# NBMC_SCHEMATIC_wout_thermistor_bridge.net
KiCad netlist of a schematic drawn in EAGLE
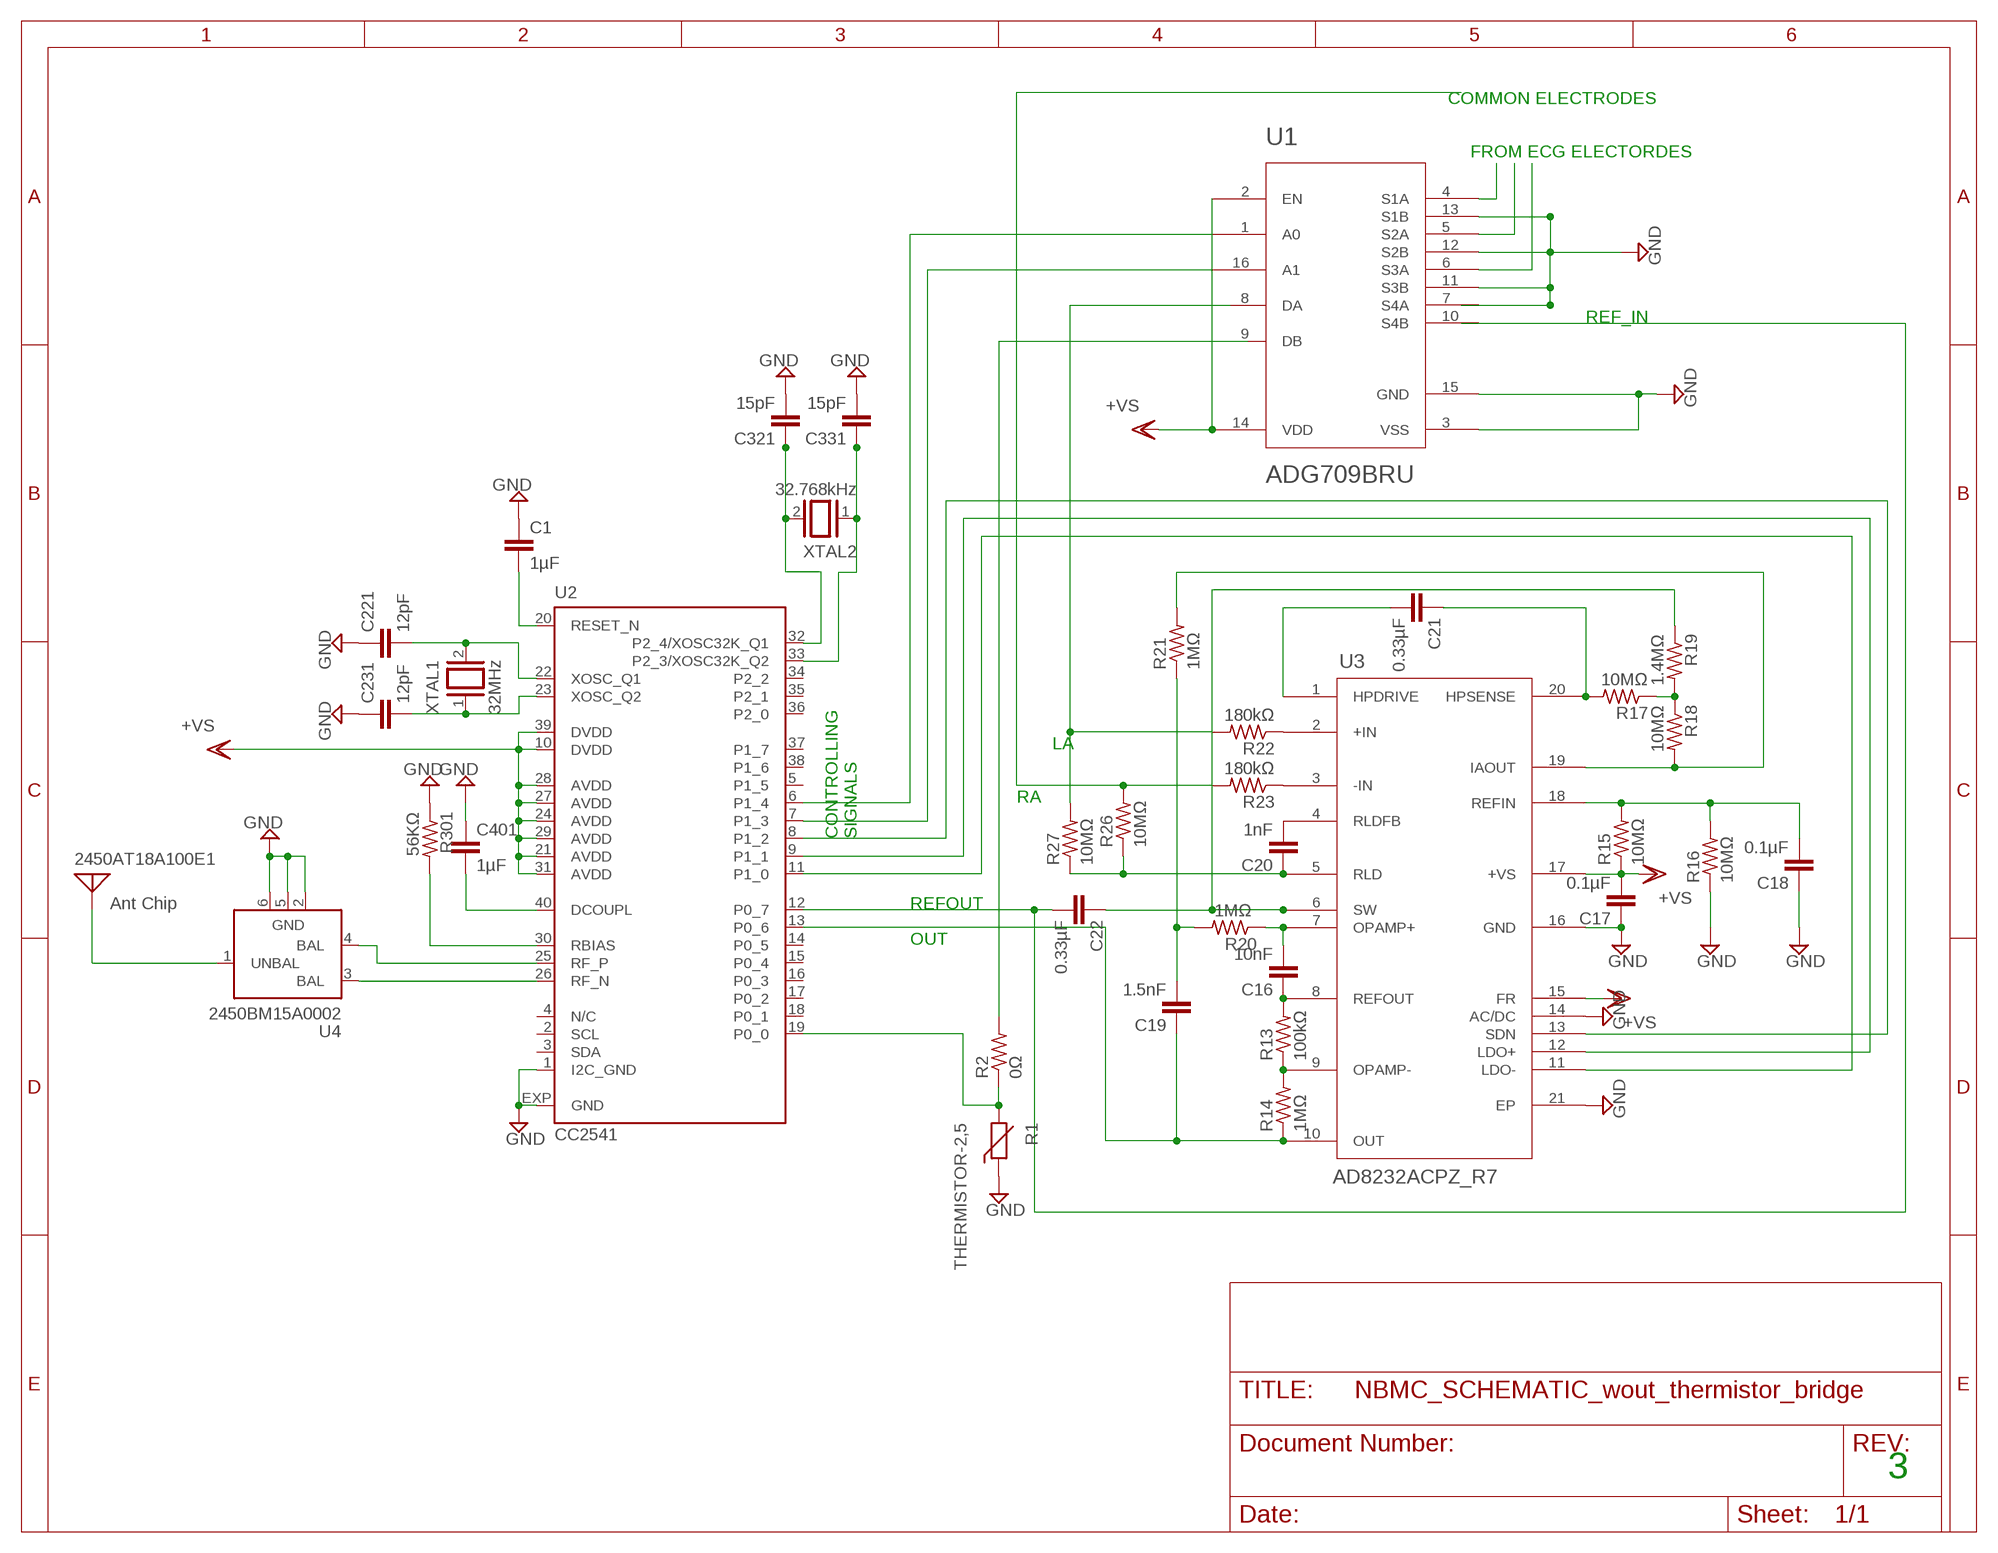
[diagram p0: schematic, sheet 1]

(export (version "E")
  (design (tool "Eeschema 10.0.6"))
  (components
    (comp (ref "2450AT18A100E1")
      (value "Ant Chip")
      (footprint "eagle-import:PAD-01")
      (libsource (lib "eagle-import") (part "ANTENNA"))
    )
    (comp (ref "C1")
      (value "1µF")
      (footprint "eagle-import:C0402")
      (libsource (lib "eagle-import") (part "C-EUC0402"))
    )
    (comp (ref "C16")
      (value "10nF")
      (footprint "eagle-import:C0402")
      (libsource (lib "eagle-import") (part "C-EUC0402"))
    )
    (comp (ref "C17")
      (value "0.1µF")
      (footprint "eagle-import:C0402")
      (libsource (lib "eagle-import") (part "C-EUC0402"))
    )
    (comp (ref "C18")
      (value "0.1µF")
      (footprint "eagle-import:C0402")
      (libsource (lib "eagle-import") (part "C-EUC0402"))
    )
    (comp (ref "C19")
      (value "1.5nF")
      (footprint "eagle-import:C0402")
      (libsource (lib "eagle-import") (part "C-EUC0402"))
    )
    (comp (ref "C20")
      (value "1nF")
      (footprint "eagle-import:C0402")
      (libsource (lib "eagle-import") (part "C-EUC0402"))
    )
    (comp (ref "C21")
      (value "0.33µF")
      (footprint "eagle-import:C0402")
      (libsource (lib "eagle-import") (part "C-EUC0402"))
    )
    (comp (ref "C22")
      (value "0.33µF")
      (footprint "eagle-import:C0402")
      (libsource (lib "eagle-import") (part "C-EUC0402"))
    )
    (comp (ref "C221")
      (value "12pF")
      (footprint "eagle-import:C0402")
      (libsource (lib "eagle-import") (part "C-EUC0402"))
    )
    (comp (ref "C231")
      (value "12pF")
      (footprint "eagle-import:C0402")
      (libsource (lib "eagle-import") (part "C-EUC0402"))
    )
    (comp (ref "C321")
      (value "15pF")
      (footprint "eagle-import:C0402")
      (libsource (lib "eagle-import") (part "C-EUC0402"))
    )
    (comp (ref "C331")
      (value "15pF")
      (footprint "eagle-import:C0402")
      (libsource (lib "eagle-import") (part "C-EUC0402"))
    )
    (comp (ref "C401")
      (value "1µF")
      (footprint "eagle-import:C0402")
      (libsource (lib "eagle-import") (part "C-EUC0402"))
    )
    (comp (ref "R1")
      (value "THERMISTOR-2,5")
      (footprint "eagle-import:RS-2,5")
      (libsource (lib "eagle-import") (part "THERMISTOR-2,5"))
    )
    (comp (ref "R2")
      (value "0Ω")
      (footprint "eagle-import:R0402")
      (libsource (lib "eagle-import") (part "R-US_R0402"))
    )
    (comp (ref "R13")
      (value "100kΩ")
      (footprint "eagle-import:R0402")
      (libsource (lib "eagle-import") (part "R-US_R0402"))
    )
    (comp (ref "R14")
      (value "1MΩ")
      (footprint "eagle-import:R0402")
      (libsource (lib "eagle-import") (part "R-US_R0402"))
    )
    (comp (ref "R15")
      (value "10MΩ")
      (footprint "eagle-import:R0402")
      (libsource (lib "eagle-import") (part "R-US_R0402"))
    )
    (comp (ref "R16")
      (value "10MΩ")
      (footprint "eagle-import:R0402")
      (libsource (lib "eagle-import") (part "R-US_R0402"))
    )
    (comp (ref "R17")
      (value "10MΩ")
      (footprint "eagle-import:R0402")
      (libsource (lib "eagle-import") (part "R-US_R0402"))
    )
    (comp (ref "R18")
      (value "10MΩ")
      (footprint "eagle-import:R0402")
      (libsource (lib "eagle-import") (part "R-US_R0402"))
    )
    (comp (ref "R19")
      (value "1.4MΩ")
      (footprint "eagle-import:R0402")
      (libsource (lib "eagle-import") (part "R-US_R0402"))
    )
    (comp (ref "R20")
      (value "1MΩ")
      (footprint "eagle-import:R0402")
      (libsource (lib "eagle-import") (part "R-US_R0402"))
    )
    (comp (ref "R21")
      (value "1MΩ")
      (footprint "eagle-import:R0402")
      (libsource (lib "eagle-import") (part "R-US_R0402"))
    )
    (comp (ref "R22")
      (value "180kΩ")
      (footprint "eagle-import:R0402")
      (libsource (lib "eagle-import") (part "R-US_R0402"))
    )
    (comp (ref "R23")
      (value "180kΩ")
      (footprint "eagle-import:R0402")
      (libsource (lib "eagle-import") (part "R-US_R0402"))
    )
    (comp (ref "R26")
      (value "10MΩ")
      (footprint "eagle-import:R0402")
      (libsource (lib "eagle-import") (part "R-US_R0402"))
    )
    (comp (ref "R27")
      (value "10MΩ")
      (footprint "eagle-import:R0402")
      (libsource (lib "eagle-import") (part "R-US_R0402"))
    )
    (comp (ref "R301")
      (value "56KΩ")
      (footprint "eagle-import:R0402")
      (libsource (lib "eagle-import") (part "R-US_R0402"))
    )
    (comp (ref "U1")
      (value "ADG709BRU")
      (footprint "eagle-import:RU_16")
      (libsource (lib "eagle-import") (part "ADG709BRU"))
    )
    (comp (ref "U2")
      (value "CC2541")
      (footprint "eagle-import:RHA_S-PVQFN-N40")
      (libsource (lib "eagle-import") (part "CC2541"))
    )
    (comp (ref "U3")
      (value "AD8232ACPZ_R7")
      (footprint "eagle-import:CP_20_10")
      (libsource (lib "eagle-import") (part "AD8232ACPZ_R7"))
    )
    (comp (ref "U4")
      (value "2450BM15A0002")
      (footprint "eagle-import:2450BM15A0002")
      (libsource (lib "eagle-import") (part "2450BM15A0002"))
    )
    (comp (ref "XTAL1")
      (value "32MHz")
      (footprint "eagle-import:Q")
      (libsource (lib "eagle-import") (part "XTAL"))
    )
    (comp (ref "XTAL2")
      (value "32.768kHz")
      (footprint "eagle-import:Q")
      (libsource (lib "eagle-import") (part "XTAL"))
    )
  )
  (nets
    (net (code "1") (name "+VS") (class "Default")
      (node (ref "C17") (pin "2") (pinfunction "2_2") (pintype "passive"))
      (node (ref "R15") (pin "1") (pinfunction "1_1") (pintype "passive"))
      (node (ref "U1") (pin "14") (pinfunction "VDD_14") (pintype "power_in"))
      (node (ref "U1") (pin "2") (pinfunction "EN_2") (pintype "passive"))
      (node (ref "U2") (pin "10") (pinfunction "DVDD_10") (pintype "power_in"))
      (node (ref "U2") (pin "21") (pinfunction "AVDD_21") (pintype "power_in"))
      (node (ref "U2") (pin "24") (pinfunction "AVDD_24") (pintype "power_in"))
      (node (ref "U2") (pin "27") (pinfunction "AVDD_27") (pintype "power_in"))
      (node (ref "U2") (pin "28") (pinfunction "AVDD_28") (pintype "power_in"))
      (node (ref "U2") (pin "29") (pinfunction "AVDD_29") (pintype "power_in"))
      (node (ref "U2") (pin "31") (pinfunction "AVDD_31") (pintype "power_in"))
      (node (ref "U2") (pin "39") (pinfunction "DVDD_39") (pintype "power_in"))
      (node (ref "U3") (pin "15") (pinfunction "FR_15") (pintype "passive"))
      (node (ref "U3") (pin "17") (pinfunction "+VS_17") (pintype "passive"))
    )
    (net (code "2") (name "/N{slash}C") (class "Default")
      (node (ref "U2") (pin "4") (pinfunction "N/C_4") (pintype "power_in"))
    )
    (net (code "3") (name "GND") (class "Default")
      (node (ref "C1") (pin "1") (pinfunction "1_1") (pintype "passive"))
      (node (ref "C17") (pin "1") (pinfunction "1_1") (pintype "passive"))
      (node (ref "C18") (pin "1") (pinfunction "1_1") (pintype "passive"))
      (node (ref "C221") (pin "1") (pinfunction "1_1") (pintype "passive"))
      (node (ref "C231") (pin "1") (pinfunction "1_1") (pintype "passive"))
      (node (ref "C321") (pin "2") (pinfunction "2_2") (pintype "passive"))
      (node (ref "C331") (pin "2") (pinfunction "2_2") (pintype "passive"))
      (node (ref "C401") (pin "1") (pinfunction "1_1") (pintype "passive"))
      (node (ref "R1") (pin "1") (pinfunction "1_1") (pintype "passive"))
      (node (ref "R16") (pin "1") (pinfunction "1_1") (pintype "passive"))
      (node (ref "R301") (pin "1") (pinfunction "1_1") (pintype "passive"))
      (node (ref "U1") (pin "11") (pinfunction "S3B_11") (pintype "passive"))
      (node (ref "U1") (pin "12") (pinfunction "S2B_12") (pintype "passive"))
      (node (ref "U1") (pin "13") (pinfunction "S1B_13") (pintype "passive"))
      (node (ref "U1") (pin "15") (pinfunction "GND_15") (pintype "passive"))
      (node (ref "U1") (pin "3") (pinfunction "VSS_3") (pintype "power_in"))
      (node (ref "U2") (pin "1") (pinfunction "I2C_GND_1") (pintype "power_in"))
      (node (ref "U2") (pin "EXP") (pinfunction "GND_EXP") (pintype "passive"))
      (node (ref "U3") (pin "14") (pinfunction "AC/DC_14") (pintype "passive"))
      (node (ref "U3") (pin "16") (pinfunction "GND_16") (pintype "passive"))
      (node (ref "U3") (pin "21") (pinfunction "EP_21") (pintype "passive"))
      (node (ref "U4") (pin "2") (pinfunction "GND_2") (pintype "passive"))
      (node (ref "U4") (pin "5") (pinfunction "GND_5") (pintype "passive"))
      (node (ref "U4") (pin "6") (pinfunction "GND_6") (pintype "passive"))
    )
    (net (code "4") (name "Net-(C19-Pad2)") (class "Default")
      (node (ref "C19") (pin "2") (pinfunction "2_2") (pintype "passive"))
      (node (ref "R20") (pin "2") (pinfunction "2_2") (pintype "passive"))
      (node (ref "R21") (pin "1") (pinfunction "1_1") (pintype "passive"))
    )
    (net (code "5") (name "Net-(R17-Pad1)") (class "Default")
      (node (ref "R17") (pin "1") (pinfunction "1_1") (pintype "passive"))
      (node (ref "R18") (pin "1") (pinfunction "1_1") (pintype "passive"))
      (node (ref "R19") (pin "2") (pinfunction "2_2") (pintype "passive"))
    )
    (net (code "6") (name "Net-(R22-Pad2)") (class "Default")
      (node (ref "R22") (pin "2") (pinfunction "2_2") (pintype "passive"))
      (node (ref "R27") (pin "2") (pinfunction "2_2") (pintype "passive"))
    )
    (net (code "7") (name "Net-(R23-Pad2)") (class "Default")
      (node (ref "R23") (pin "2") (pinfunction "2_2") (pintype "passive"))
      (node (ref "R26") (pin "2") (pinfunction "2_2") (pintype "passive"))
    )
    (net (code "8") (name "Net-(U1-A0)") (class "Default")
      (node (ref "U1") (pin "1") (pinfunction "A0_1") (pintype "passive"))
      (node (ref "U2") (pin "6") (pinfunction "P1_4_6") (pintype "bidirectional"))
    )
    (net (code "9") (name "Net-(U1-A1)") (class "Default")
      (node (ref "U1") (pin "16") (pinfunction "A1_16") (pintype "passive"))
      (node (ref "U2") (pin "7") (pinfunction "P1_3_7") (pintype "bidirectional"))
    )
    (net (code "10") (name "Net-(U1-S4B)") (class "Default")
      (node (ref "C22") (pin "2") (pinfunction "2_2") (pintype "passive"))
      (node (ref "U1") (pin "10") (pinfunction "S4B_10") (pintype "passive"))
      (node (ref "U2") (pin "12") (pinfunction "P0_7_12") (pintype "bidirectional"))
    )
    (net (code "11") (name "Net-(U2-DCOUPL)") (class "Default")
      (node (ref "C401") (pin "2") (pinfunction "2_2") (pintype "passive"))
      (node (ref "U2") (pin "40") (pinfunction "DCOUPL_40") (pintype "power_in"))
    )
    (net (code "12") (name "Net-(U2-P0_0)") (class "Default")
      (node (ref "R1") (pin "2") (pinfunction "2_2") (pintype "passive"))
      (node (ref "R2") (pin "1") (pinfunction "1_1") (pintype "passive"))
      (node (ref "U2") (pin "19") (pinfunction "P0_0_19") (pintype "bidirectional"))
    )
    (net (code "13") (name "Net-(U2-P0_6)") (class "Default")
      (node (ref "C19") (pin "1") (pinfunction "1_1") (pintype "passive"))
      (node (ref "R14") (pin "1") (pinfunction "1_1") (pintype "passive"))
      (node (ref "U2") (pin "13") (pinfunction "P0_6_13") (pintype "bidirectional"))
      (node (ref "U3") (pin "10") (pinfunction "OUT_10") (pintype "passive"))
    )
    (net (code "14") (name "Net-(U2-P1_0)") (class "Default")
      (node (ref "U2") (pin "11") (pinfunction "P1_0_11") (pintype "bidirectional"))
      (node (ref "U3") (pin "11") (pinfunction "LDO-_11") (pintype "passive"))
    )
    (net (code "15") (name "Net-(U2-P1_1)") (class "Default")
      (node (ref "U2") (pin "9") (pinfunction "P1_1_9") (pintype "bidirectional"))
      (node (ref "U3") (pin "12") (pinfunction "LDO+_12") (pintype "passive"))
    )
    (net (code "16") (name "Net-(U2-P1_2)") (class "Default")
      (node (ref "U2") (pin "8") (pinfunction "P1_2_8") (pintype "bidirectional"))
      (node (ref "U3") (pin "13") (pinfunction "SDN_13") (pintype "passive"))
    )
    (net (code "17") (name "Net-(U2-P2_3{slash}XOSC32K_Q2)") (class "Default")
      (node (ref "C331") (pin "1") (pinfunction "1_1") (pintype "passive"))
      (node (ref "U2") (pin "33") (pinfunction "P2_3/XOSC32K_Q2_33") (pintype "bidirectional"))
      (node (ref "XTAL2") (pin "1") (pinfunction "1_1") (pintype "passive"))
    )
    (net (code "18") (name "Net-(U2-P2_4{slash}XOSC32K_Q1)") (class "Default")
      (node (ref "C321") (pin "1") (pinfunction "1_1") (pintype "passive"))
      (node (ref "U2") (pin "32") (pinfunction "P2_4/XOSC32K_Q1_32") (pintype "bidirectional"))
      (node (ref "XTAL2") (pin "2") (pinfunction "2_2") (pintype "passive"))
    )
    (net (code "19") (name "Net-(U2-RBIAS)") (class "Default")
      (node (ref "R301") (pin "2") (pinfunction "2_2") (pintype "passive"))
      (node (ref "U2") (pin "30") (pinfunction "RBIAS_30") (pintype "bidirectional"))
    )
    (net (code "20") (name "Net-(U2-RESET_N)") (class "Default")
      (node (ref "C1") (pin "2") (pinfunction "2_2") (pintype "passive"))
      (node (ref "U2") (pin "20") (pinfunction "RESET_N_20") (pintype "input"))
    )
    (net (code "21") (name "Net-(U2-RF_N)") (class "Default")
      (node (ref "U2") (pin "26") (pinfunction "RF_N_26") (pintype "bidirectional"))
      (node (ref "U4") (pin "3") (pinfunction "BAL_3") (pintype "passive"))
    )
    (net (code "22") (name "Net-(U2-RF_P)") (class "Default")
      (node (ref "U2") (pin "25") (pinfunction "RF_P_25") (pintype "bidirectional"))
      (node (ref "U4") (pin "4") (pinfunction "BAL_4") (pintype "passive"))
    )
    (net (code "23") (name "Net-(U2-XOSC_Q1)") (class "Default")
      (node (ref "C221") (pin "2") (pinfunction "2_2") (pintype "passive"))
      (node (ref "U2") (pin "22") (pinfunction "XOSC_Q1_22") (pintype "bidirectional"))
      (node (ref "XTAL1") (pin "2") (pinfunction "2_2") (pintype "passive"))
    )
    (net (code "24") (name "Net-(U2-XOSC_Q2)") (class "Default")
      (node (ref "C231") (pin "2") (pinfunction "2_2") (pintype "passive"))
      (node (ref "U2") (pin "23") (pinfunction "XOSC_Q2_23") (pintype "bidirectional"))
      (node (ref "XTAL1") (pin "1") (pinfunction "1_1") (pintype "passive"))
    )
    (net (code "25") (name "Net-(U3-+IN)") (class "Default")
      (node (ref "R22") (pin "1") (pinfunction "1_1") (pintype "passive"))
      (node (ref "U3") (pin "2") (pinfunction "+IN_2") (pintype "passive"))
    )
    (net (code "26") (name "Net-(U3--IN)") (class "Default")
      (node (ref "R23") (pin "1") (pinfunction "1_1") (pintype "passive"))
      (node (ref "U3") (pin "3") (pinfunction "-IN_3") (pintype "passive"))
    )
    (net (code "27") (name "Net-(U3-HPDRIVE)") (class "Default")
      (node (ref "C21") (pin "2") (pinfunction "2_2") (pintype "passive"))
      (node (ref "U3") (pin "1") (pinfunction "HPDRIVE_1") (pintype "passive"))
    )
    (net (code "28") (name "Net-(U3-HPSENSE)") (class "Default")
      (node (ref "C21") (pin "1") (pinfunction "1_1") (pintype "passive"))
      (node (ref "R17") (pin "2") (pinfunction "2_2") (pintype "passive"))
      (node (ref "U3") (pin "20") (pinfunction "HPSENSE_20") (pintype "passive"))
    )
    (net (code "29") (name "Net-(U3-IAOUT)") (class "Default")
      (node (ref "R18") (pin "2") (pinfunction "2_2") (pintype "passive"))
      (node (ref "R21") (pin "2") (pinfunction "2_2") (pintype "passive"))
      (node (ref "U3") (pin "19") (pinfunction "IAOUT_19") (pintype "passive"))
    )
    (net (code "30") (name "Net-(U3-OPAMP+)") (class "Default")
      (node (ref "C16") (pin "2") (pinfunction "2_2") (pintype "passive"))
      (node (ref "R20") (pin "1") (pinfunction "1_1") (pintype "passive"))
      (node (ref "U3") (pin "7") (pinfunction "OPAMP+_7") (pintype "passive"))
    )
    (net (code "31") (name "Net-(U3-OPAMP-)") (class "Default")
      (node (ref "R13") (pin "1") (pinfunction "1_1") (pintype "passive"))
      (node (ref "R14") (pin "2") (pinfunction "2_2") (pintype "passive"))
      (node (ref "U3") (pin "9") (pinfunction "OPAMP-_9") (pintype "passive"))
    )
    (net (code "32") (name "Net-(U3-REFIN)") (class "Default")
      (node (ref "C18") (pin "2") (pinfunction "2_2") (pintype "passive"))
      (node (ref "R15") (pin "2") (pinfunction "2_2") (pintype "passive"))
      (node (ref "R16") (pin "2") (pinfunction "2_2") (pintype "passive"))
      (node (ref "U3") (pin "18") (pinfunction "REFIN_18") (pintype "passive"))
    )
    (net (code "33") (name "Net-(U3-REFOUT)") (class "Default")
      (node (ref "C16") (pin "1") (pinfunction "1_1") (pintype "passive"))
      (node (ref "R13") (pin "2") (pinfunction "2_2") (pintype "passive"))
      (node (ref "U3") (pin "8") (pinfunction "REFOUT_8") (pintype "passive"))
    )
    (net (code "34") (name "Net-(U3-RLD)") (class "Default")
      (node (ref "C20") (pin "1") (pinfunction "1_1") (pintype "passive"))
      (node (ref "R26") (pin "1") (pinfunction "1_1") (pintype "passive"))
      (node (ref "R27") (pin "1") (pinfunction "1_1") (pintype "passive"))
      (node (ref "U3") (pin "5") (pinfunction "RLD_5") (pintype "passive"))
    )
    (net (code "35") (name "Net-(U3-RLDFB)") (class "Default")
      (node (ref "C20") (pin "2") (pinfunction "2_2") (pintype "passive"))
      (node (ref "U3") (pin "4") (pinfunction "RLDFB_4") (pintype "passive"))
    )
    (net (code "36") (name "Net-(U3-SW)") (class "Default")
      (node (ref "C22") (pin "1") (pinfunction "1_1") (pintype "passive"))
      (node (ref "R19") (pin "1") (pinfunction "1_1") (pintype "passive"))
      (node (ref "U3") (pin "6") (pinfunction "SW_6") (pintype "passive"))
    )
    (net (code "37") (name "Net-(U4-UNBAL)") (class "Default")
      (node (ref "2450AT18A100E1") (pin "1") (pinfunction "1_1") (pintype "output"))
      (node (ref "U4") (pin "1") (pinfunction "UNBAL_1") (pintype "passive"))
    )
    (net (code "38") (name "unconnected-(R2-Pad2)") (class "Default")
      (node (ref "R2") (pin "2") (pinfunction "2_2") (pintype "passive"))
    )
    (net (code "39") (name "unconnected-(U1-DA-Pad8)") (class "Default")
      (node (ref "U1") (pin "8") (pinfunction "DA_8") (pintype "passive"))
    )
    (net (code "40") (name "unconnected-(U1-DB-Pad9)") (class "Default")
      (node (ref "U1") (pin "9") (pinfunction "DB_9") (pintype "passive"))
    )
    (net (code "41") (name "unconnected-(U1-S1A-Pad4)") (class "Default")
      (node (ref "U1") (pin "4") (pinfunction "S1A_4") (pintype "passive"))
    )
    (net (code "42") (name "unconnected-(U1-S2A-Pad5)") (class "Default")
      (node (ref "U1") (pin "5") (pinfunction "S2A_5") (pintype "passive"))
    )
    (net (code "43") (name "unconnected-(U1-S3A-Pad6)") (class "Default")
      (node (ref "U1") (pin "6") (pinfunction "S3A_6") (pintype "passive"))
    )
    (net (code "44") (name "unconnected-(U1-S4A-Pad7)") (class "Default")
      (node (ref "U1") (pin "7") (pinfunction "S4A_7") (pintype "passive"))
    )
    (net (code "45") (name "unconnected-(U2-P0_1-Pad18)") (class "Default")
      (node (ref "U2") (pin "18") (pinfunction "P0_1_18") (pintype "bidirectional"))
    )
    (net (code "46") (name "unconnected-(U2-P0_2-Pad17)") (class "Default")
      (node (ref "U2") (pin "17") (pinfunction "P0_2_17") (pintype "bidirectional"))
    )
    (net (code "47") (name "unconnected-(U2-P0_3-Pad16)") (class "Default")
      (node (ref "U2") (pin "16") (pinfunction "P0_3_16") (pintype "bidirectional"))
    )
    (net (code "48") (name "unconnected-(U2-P0_4-Pad15)") (class "Default")
      (node (ref "U2") (pin "15") (pinfunction "P0_4_15") (pintype "bidirectional"))
    )
    (net (code "49") (name "unconnected-(U2-P0_5-Pad14)") (class "Default")
      (node (ref "U2") (pin "14") (pinfunction "P0_5_14") (pintype "bidirectional"))
    )
    (net (code "50") (name "unconnected-(U2-P1_5-Pad5)") (class "Default")
      (node (ref "U2") (pin "5") (pinfunction "P1_5_5") (pintype "bidirectional"))
    )
    (net (code "51") (name "unconnected-(U2-P1_6-Pad38)") (class "Default")
      (node (ref "U2") (pin "38") (pinfunction "P1_6_38") (pintype "bidirectional"))
    )
    (net (code "52") (name "unconnected-(U2-P1_7-Pad37)") (class "Default")
      (node (ref "U2") (pin "37") (pinfunction "P1_7_37") (pintype "bidirectional"))
    )
    (net (code "53") (name "unconnected-(U2-P2_0-Pad36)") (class "Default")
      (node (ref "U2") (pin "36") (pinfunction "P2_0_36") (pintype "bidirectional"))
    )
    (net (code "54") (name "unconnected-(U2-P2_1-Pad35)") (class "Default")
      (node (ref "U2") (pin "35") (pinfunction "P2_1_35") (pintype "bidirectional"))
    )
    (net (code "55") (name "unconnected-(U2-P2_2-Pad34)") (class "Default")
      (node (ref "U2") (pin "34") (pinfunction "P2_2_34") (pintype "bidirectional"))
    )
    (net (code "56") (name "unconnected-(U2-SCL-Pad2)") (class "Default")
      (node (ref "U2") (pin "2") (pinfunction "SCL_2") (pintype "bidirectional"))
    )
    (net (code "57") (name "unconnected-(U2-SDA-Pad3)") (class "Default")
      (node (ref "U2") (pin "3") (pinfunction "SDA_3") (pintype "bidirectional"))
    )
  )
)
